# AirScout_SchematicsV2_1.net
KiCad netlist of a schematic drawn in Altium Designer
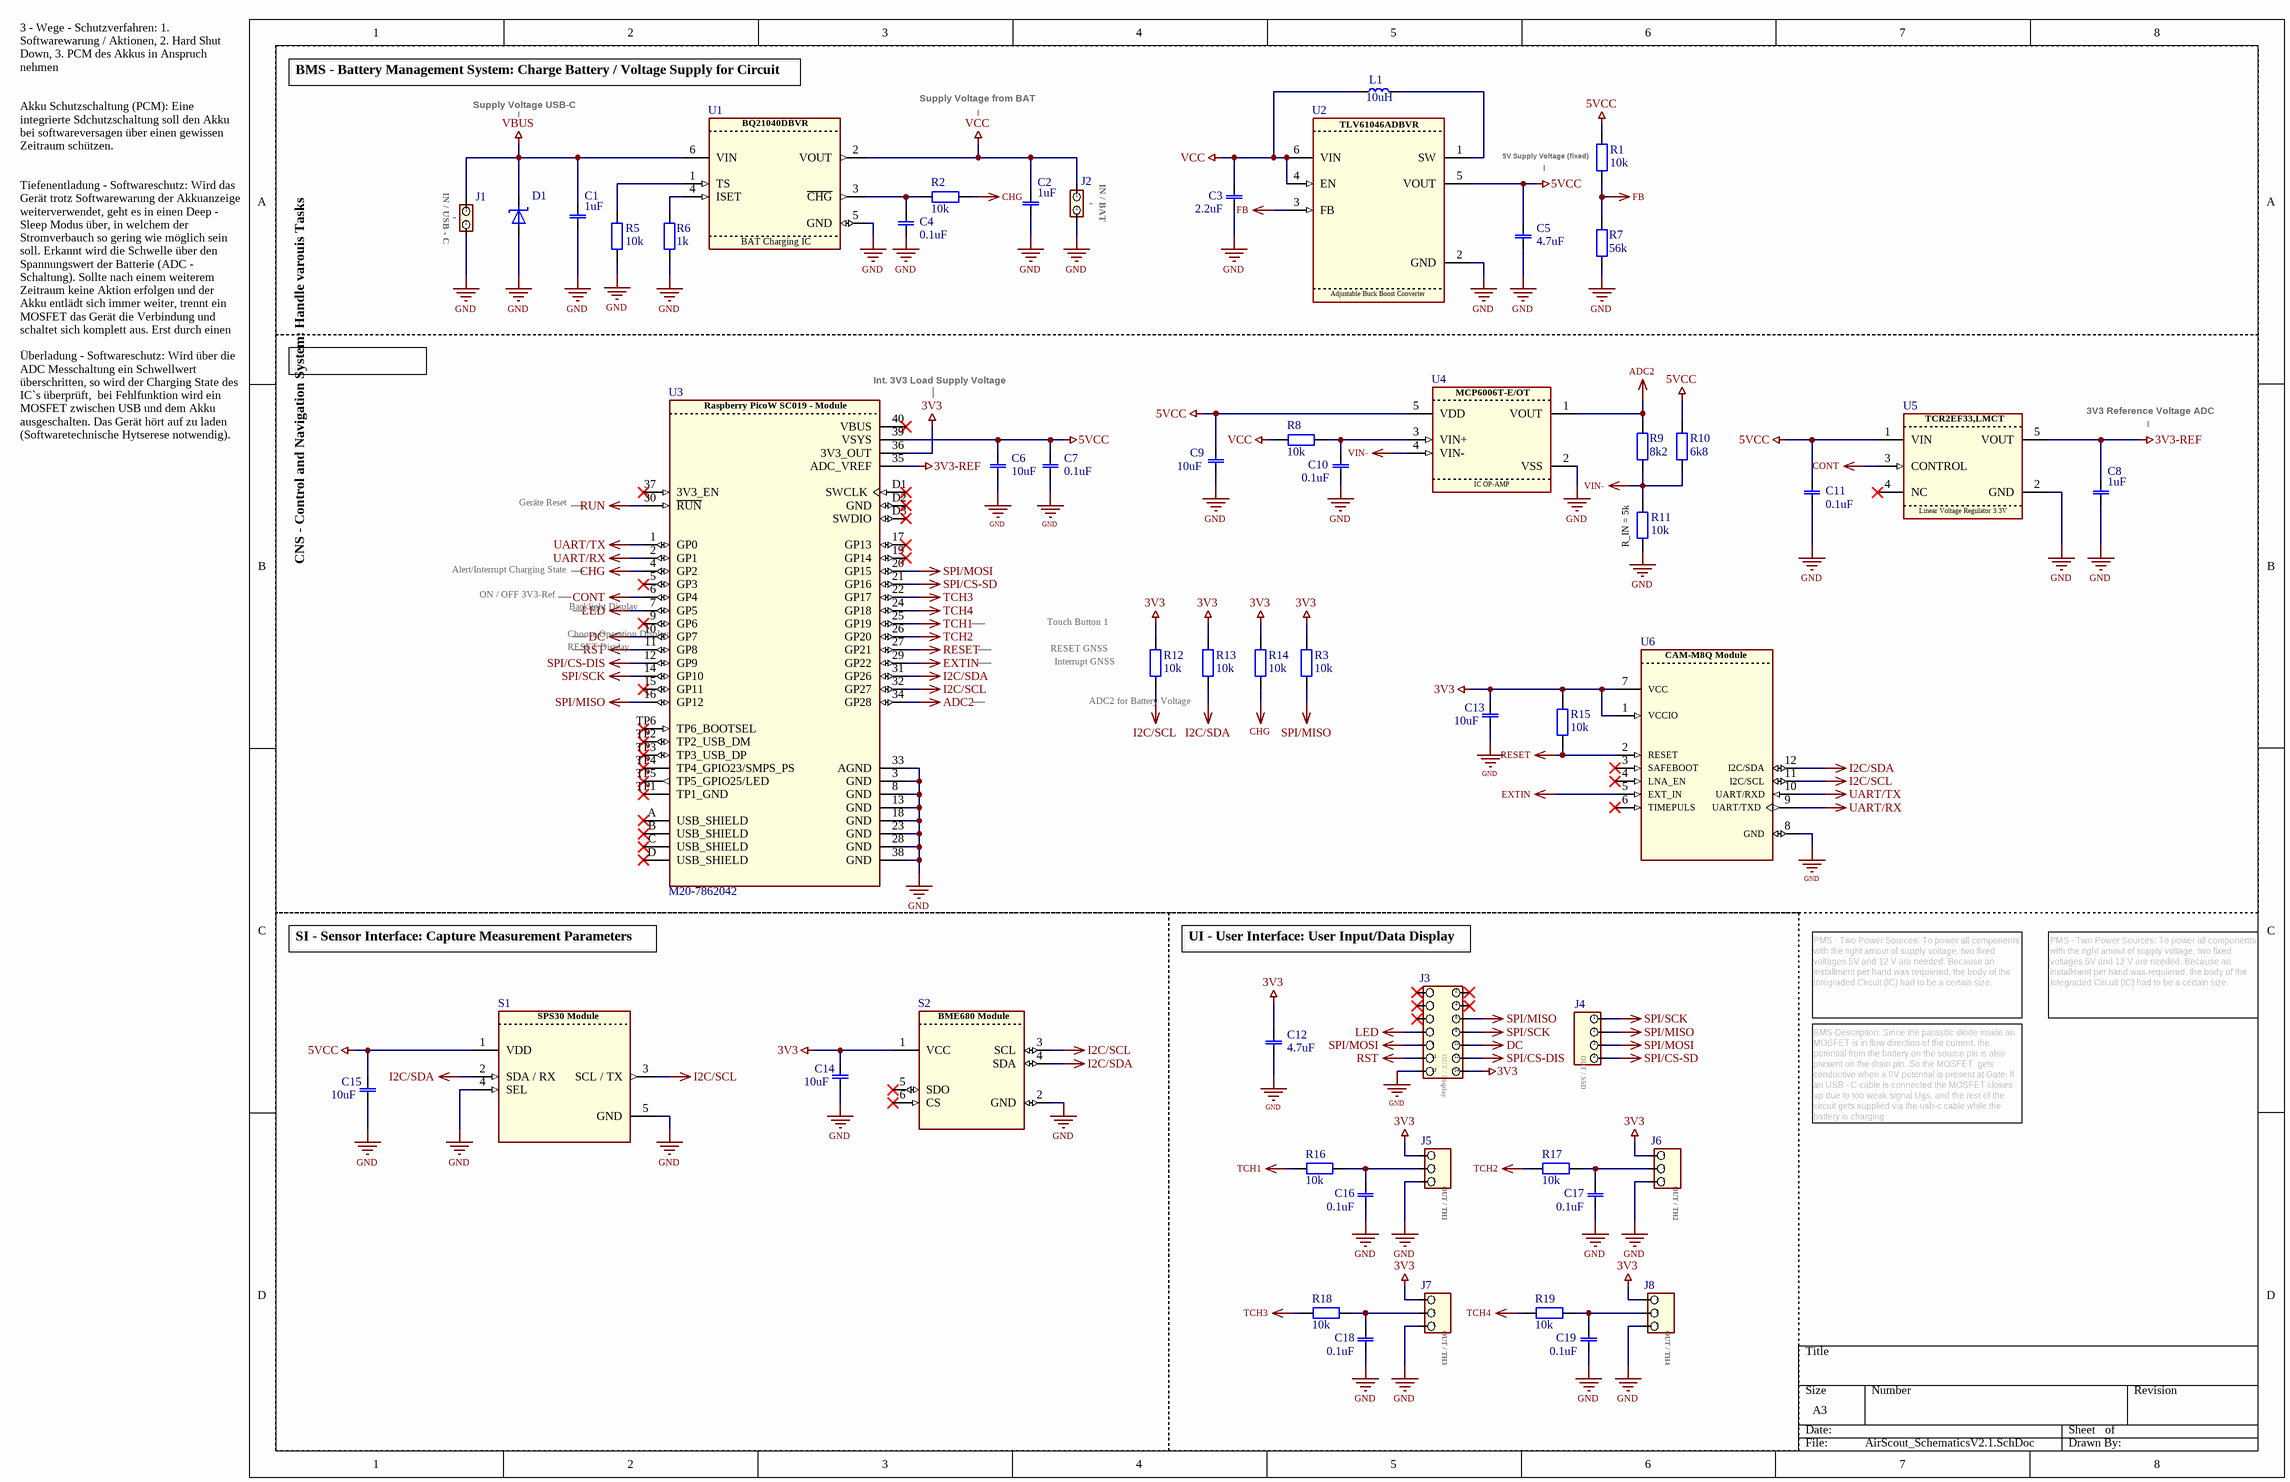
[diagram p0: AirScout_SchematicsV2.1.SchDoc]

(export (version "E")
  (design (tool "Eeschema 10.0.6"))
  (components
    (comp (ref "C1")
      (value "1uF")
      (footprint "CAPC340180_140N_KEM")
      (description "CAP CER 1UF 25V X7R 1206")
      (fields (field (name "Comment") "C1206C105K3RACTU"))
      (libsource (lib "AirScoutSchLibV2.0") (part "CAP"))
    )
    (comp (ref "C2")
      (value "1uF")
      (footprint "CAPC340180_140N_KEM")
      (description "CAP CER 1UF 25V X7R 1206")
      (fields (field (name "Comment") "C1206C105K3RACTU"))
      (libsource (lib "AirScoutSchLibV2.0") (part "CAP"))
    )
    (comp (ref "C3")
      (value "2.2uF")
      (footprint "CAPC340180_140N_KEM")
      (description "CAP CER 2.2UF 50V X7R 1206")
      (fields (field (name "Comment") "CL31B225KBHNNNE"))
      (libsource (lib "AirScoutSchLibV2.0") (part "CAP"))
    )
    (comp (ref "C4")
      (value "0.1uF")
      (footprint "CAPC340180_140N_KEM")
      (description "CAP CER 0.1UF 50V X7R 1206")
      (fields (field (name "Comment") "C1206C104K5RACTU"))
      (libsource (lib "AirScoutSchLibV2.0") (part "CAP"))
    )
    (comp (ref "C5")
      (value "4.7uF")
      (footprint "CAPC340180_140N_KEM")
      (description "CAP CER 4.7UF 50V X7R 1206")
      (fields (field (name "Comment") "CL31B475KBHNFNE"))
      (libsource (lib "AirScoutSchLibV2.0") (part "CAP"))
    )
    (comp (ref "C6")
      (value "10uF")
      (footprint "CAPC340180_140N_KEM")
      (description "CAP CER 10UF 25V X7R 1206")
      (fields (field (name "Comment") "CL31B106KAHNNNE"))
      (libsource (lib "AirScoutSchLibV2.0") (part "CAP"))
    )
    (comp (ref "C7")
      (value "0.1uF")
      (footprint "CAPC340180_140N_KEM")
      (description "CAP CER 0.1UF 50V X7R 1206")
      (fields (field (name "Comment") "C1206C104K5RACTU"))
      (libsource (lib "AirScoutSchLibV2.0") (part "CAP"))
    )
    (comp (ref "C8")
      (value "1uF")
      (footprint "CAPC340180_140N_KEM")
      (description "CAP CER 1UF 25V X7R 1206")
      (fields (field (name "Comment") "C1206C105K3RACTU"))
      (libsource (lib "AirScoutSchLibV2.0") (part "CAP"))
    )
    (comp (ref "C9")
      (value "10uF")
      (footprint "CAPC340180_140N_KEM")
      (description "CAP CER 10UF 25V X7R 1206")
      (fields (field (name "Comment") "CL31B106KAHNNNE"))
      (libsource (lib "AirScoutSchLibV2.0") (part "CAP"))
    )
    (comp (ref "C10")
      (value "0.1uF")
      (footprint "CAPC340180_140N_KEM")
      (description "CAP CER 0.1UF 50V X7R 1206")
      (fields (field (name "Comment") "C1206C104K5RACTU"))
      (libsource (lib "AirScoutSchLibV2.0") (part "CAP"))
    )
    (comp (ref "C11")
      (value "0.1uF")
      (footprint "CAPC340180_140N_KEM")
      (description "CAP CER 0.1UF 50V X7R 1206")
      (fields (field (name "Comment") "C1206C104K5RACTU"))
      (libsource (lib "AirScoutSchLibV2.0") (part "CAP"))
    )
    (comp (ref "C12")
      (value "4.7uF")
      (footprint "CAPC340180_140N_KEM")
      (description "CAP CER 4.7UF 50V X7R 1206")
      (fields (field (name "Comment") "CL31B475KBHNFNE"))
      (libsource (lib "AirScoutSchLibV2.0") (part "CAP"))
    )
    (comp (ref "C13")
      (value "10uF")
      (footprint "CAPC340180_140N_KEM")
      (description "CAP CER 10UF 25V X7R 1206")
      (fields (field (name "Comment") "CL31B106KAHNNNE"))
      (libsource (lib "AirScoutSchLibV2.0") (part "CAP"))
    )
    (comp (ref "C14")
      (value "10uF")
      (footprint "CAPC340180_140N_KEM")
      (description "CAP CER 10UF 25V X7R 1206")
      (fields (field (name "Comment") "CL31B106KAHNNNE"))
      (libsource (lib "AirScoutSchLibV2.0") (part "CAP"))
    )
    (comp (ref "C15")
      (value "10uF")
      (footprint "CAPC340180_140N_KEM")
      (description "CAP CER 10UF 25V X7R 1206")
      (fields (field (name "Comment") "CL31B106KAHNNNE"))
      (libsource (lib "AirScoutSchLibV2.0") (part "CAP"))
    )
    (comp (ref "C16")
      (value "0.1uF")
      (footprint "CAPC340180_140N_KEM")
      (description "CAP CER 0.1UF 50V X7R 1206")
      (fields (field (name "Comment") "C1206C104K5RACTU"))
      (libsource (lib "AirScoutSchLibV2.0") (part "CAP"))
    )
    (comp (ref "C17")
      (value "0.1uF")
      (footprint "CAPC340180_140N_KEM")
      (description "CAP CER 0.1UF 50V X7R 1206")
      (fields (field (name "Comment") "C1206C104K5RACTU"))
      (libsource (lib "AirScoutSchLibV2.0") (part "CAP"))
    )
    (comp (ref "C18")
      (value "0.1uF")
      (footprint "CAPC340180_140N_KEM")
      (description "CAP CER 0.1UF 50V X7R 1206")
      (fields (field (name "Comment") "C1206C104K5RACTU"))
      (libsource (lib "AirScoutSchLibV2.0") (part "CAP"))
    )
    (comp (ref "C19")
      (value "0.1uF")
      (footprint "CAPC340180_140N_KEM")
      (description "CAP CER 0.1UF 50V X7R 1206")
      (fields (field (name "Comment") "C1206C104K5RACTU"))
      (libsource (lib "AirScoutSchLibV2.0") (part "CAP"))
    )
    (comp (ref "D1")
      (value "SMBJ14CA-13-F")
      (footprint "SMB_DIO")
      (description "TVS DIODE 14VWM 23.2VC SMB")
      (libsource (lib "AirScoutSchLibV2.1") (part "Diode-Schottky"))
    )
    (comp (ref "J1")
      (value "S2B-ZR-SM4A-TF")
      (footprint "JST_S2B-ZR-SM4A-TF")
      (description "CONN HEADER SMD R/A 2POS 1.5MM")
      (libsource (lib "AirScoutSchLibV2.2") (part "CON2x1_vertical"))
    )
    (comp (ref "J2")
      (value "S2B-ZR-SM4A-TF")
      (footprint "JST_S2B-ZR-SM4A-TF")
      (description "CONN HEADER SMD R/A 2POS 1.5MM")
      (libsource (lib "AirScoutSchLibV2.2") (part "CON2x1_vertical"))
    )
    (comp (ref "J3")
      (value "IDMS-14-D-02.00-R")
      (footprint "CONN_14POL_SAMTEC")
      (description "Alternitives: IDMS-14-D-03.00, IDMS-14-D-02.00, IDMS-14-D-03.00-R")
      (libsource (lib "AirScoutSchLibV2.0") (part "CON7x2"))
    )
    (comp (ref "J4")
      (value "IDMS-4-D-02.00-R")
      (footprint "SAMTEC_IDMS-04-S-02.00")
      (description "Alternitives:  IDMS-4-D-03.00, IDMS-4-D-02.00, IDMS-4-D-03.00-R")
      (libsource (lib "AirScoutSchLibV2.0") (part "CON 4x1"))
    )
    (comp (ref "J5")
      (value "IDMS-3-D-02.00-R")
      (footprint "CONN_3POL_SAMTEC")
      (description "Alternitives:  IDMS-3-D-03.00, IDMS-3-D-02.00, IDMS-3-D-03.00-R")
      (libsource (lib "AirScoutSchLibV2.0") (part "CON 3x1"))
    )
    (comp (ref "J6")
      (value "IDMS-3-D-02.00-R")
      (footprint "CONN_3POL_SAMTEC")
      (description "Alternitives:  IDMS-3-D-03.00, IDMS-3-D-02.00, IDMS-3-D-03.00-R")
      (libsource (lib "AirScoutSchLibV2.0") (part "CON 3x1"))
    )
    (comp (ref "J7")
      (value "IDMS-3-D-02.00-R")
      (footprint "CONN_3POL_SAMTEC")
      (description "Alternitives:  IDMS-3-D-03.00, IDMS-3-D-02.00, IDMS-3-D-03.00-R")
      (libsource (lib "AirScoutSchLibV2.0") (part "CON 3x1"))
    )
    (comp (ref "J8")
      (value "IDMS-3-D-02.00-R")
      (footprint "CONN_3POL_SAMTEC")
      (description "Alternitives:  IDMS-3-D-03.00, IDMS-3-D-02.00, IDMS-3-D-03.00-R")
      (libsource (lib "AirScoutSchLibV2.0") (part "CON 3x1"))
    )
    (comp (ref "L1")
      (value "10uH")
      (footprint "IND_FDSD0420-H-100M=P3")
      (description "FIXED IND 10UH 2A 216 MOHM SMD; \r\nAIUR-05-100K")
      (fields (field (name "Comment") "PA4332.103NLT"))
      (libsource (lib "AirScoutSchLibV2.0") (part "Inductor"))
    )
    (comp (ref "R1")
      (value "10k")
      (footprint "RESC3116X65N")
      (description "RES 10K OHM 1% 1/4W 1206")
      (fields (field (name "Comment") "RC1206FR-0710KL"))
      (libsource (lib "AirScoutSchLibV2.0") (part "RES"))
    )
    (comp (ref "R2")
      (value "10k")
      (footprint "RESC3116X65N")
      (description "RES 10K OHM 1% 1/4W 1206")
      (fields (field (name "Comment") "RC1206FR-0710KL"))
      (libsource (lib "AirScoutSchLibV2.0") (part "RES"))
    )
    (comp (ref "R3")
      (value "10k")
      (footprint "RESC3116X65N")
      (description "RES 10K OHM 1% 1/4W 1206")
      (fields (field (name "Comment") "RC1206FR-0710KL"))
      (libsource (lib "AirScoutSchLibV2.0") (part "RES"))
    )
    (comp (ref "R5")
      (value "10k")
      (footprint "RESC3116X65N")
      (description "RES 10K OHM 1% 1/4W 1206")
      (fields (field (name "Comment") "RC1206FR-0710KL"))
      (libsource (lib "AirScoutSchLibV2.0") (part "RES"))
    )
    (comp (ref "R6")
      (value "1k")
      (footprint "RESC3116X65N")
      (description "RES 1K OHM 1% 1/2W 1206")
      (fields (field (name "Comment") "RNCP1206FTD1K00"))
      (libsource (lib "AirScoutSchLibV2.0") (part "RES"))
    )
    (comp (ref "R7")
      (value "56k")
      (footprint "RESC3116X65N")
      (description "RES 56K OHM 5% 1/4W 1206")
      (fields (field (name "Comment") "RMCF1206JT56K0"))
      (libsource (lib "AirScoutSchLibV2.0") (part "RES"))
    )
    (comp (ref "R8")
      (value "10k")
      (footprint "RESC3116X65N")
      (description "RES 10K OHM 1% 1/4W 1206")
      (fields (field (name "Comment") "RC1206FR-0710KL"))
      (libsource (lib "AirScoutSchLibV2.0") (part "RES"))
    )
    (comp (ref "R9")
      (value "8k2")
      (footprint "RESC3116X65N")
      (description "RES 200K OHM 5% 1/4W 1206")
      (fields (field (name "Comment") "RC1206JR-07200KL"))
      (libsource (lib "AirScoutSchLibV2.0") (part "RES"))
    )
    (comp (ref "R10")
      (value "6k8")
      (footprint "RESC3116X65N")
      (description "RES 220K OHM 5% 1/4W 1206")
      (fields (field (name "Comment") "RC1206JR-07220KL"))
      (libsource (lib "AirScoutSchLibV2.0") (part "RES"))
    )
    (comp (ref "R11")
      (value "10k")
      (footprint "RESC3116X65N")
      (description "RES 220K OHM 5% 1/4W 1206")
      (fields (field (name "Comment") "RC1206JR-07220KL"))
      (libsource (lib "AirScoutSchLibV2.0") (part "RES"))
    )
    (comp (ref "R12")
      (value "10k")
      (footprint "RESC3116X65N")
      (description "RES 10K OHM 1% 1/4W 1206")
      (fields (field (name "Comment") "RC1206FR-0710KL"))
      (libsource (lib "AirScoutSchLibV2.0") (part "RES"))
    )
    (comp (ref "R13")
      (value "10k")
      (footprint "RESC3116X65N")
      (description "RES 10K OHM 1% 1/4W 1206")
      (fields (field (name "Comment") "RC1206FR-0710KL"))
      (libsource (lib "AirScoutSchLibV2.0") (part "RES"))
    )
    (comp (ref "R14")
      (value "10k")
      (footprint "RESC3116X65N")
      (description "RES 10K OHM 1% 1/4W 1206")
      (fields (field (name "Comment") "RC1206FR-0710KL"))
      (libsource (lib "AirScoutSchLibV2.0") (part "RES"))
    )
    (comp (ref "R15")
      (value "10k")
      (footprint "RESC3116X65N")
      (description "RES 10K OHM 1% 1/4W 1206")
      (fields (field (name "Comment") "RC1206FR-0710KL"))
      (libsource (lib "AirScoutSchLibV2.0") (part "RES"))
    )
    (comp (ref "R16")
      (value "10k")
      (footprint "RESC3116X65N")
      (description "RES 10K OHM 1% 1/4W 1206")
      (fields (field (name "Comment") "RC1206FR-0710KL"))
      (libsource (lib "AirScoutSchLibV2.0") (part "RES"))
    )
    (comp (ref "R17")
      (value "10k")
      (footprint "RESC3116X65N")
      (description "RES 10K OHM 1% 1/4W 1206")
      (fields (field (name "Comment") "RC1206FR-0710KL"))
      (libsource (lib "AirScoutSchLibV2.0") (part "RES"))
    )
    (comp (ref "R18")
      (value "10k")
      (footprint "RESC3116X65N")
      (description "RES 10K OHM 1% 1/4W 1206")
      (fields (field (name "Comment") "RC1206FR-0710KL"))
      (libsource (lib "AirScoutSchLibV2.0") (part "RES"))
    )
    (comp (ref "R19")
      (value "10k")
      (footprint "RESC3116X65N")
      (description "RES 10K OHM 1% 1/4W 1206")
      (fields (field (name "Comment") "RC1206FR-0710KL"))
      (libsource (lib "AirScoutSchLibV2.0") (part "RES"))
    )
    (comp (ref "S1")
      (value "B5B-ZR")
      (footprint "CONN5_B5B-ZR_JST")
      (description "Plug: CONN HEADER VERT 5POS 1.5MM; Air Sensor Dust Sensor Box SPS30 Module: 1649-1106-ND")
      (libsource (lib "AirScoutSchLibV2.0") (part "SPS30 Module"))
    )
    (comp (ref "S2")
      (value "NPPC061KFXC-RC")
      (footprint "PIM357")
      (libsource (lib "AirScoutSchLibV2.0") (part "BME680 Module"))
    )
    (comp (ref "U1")
      (value "BQ21040DBVR")
      (footprint "SOT95P280X145-6N")
      (fields (field (name "MF") "Texas Instruments"))
      (libsource (lib "AirScoutSchLibV2.0") (part "BQ21040DBVR"))
    )
    (comp (ref "U2")
      (value "TLV61046ADBVR")
      (footprint "DBV0006A_M")
      (description "28-V Output Voltage Boost Converter with Power Diode and Isolation Switch 6-SOT-23 -40 to 125")
      (fields (field (name "COPYRIGHT") "Copyright (C) 2025 Ultra Librarian. All rights reserved."))
      (libsource (lib "AirScoutSchLibV2.0") (part "TLV61046ADBVR"))
    )
    (comp (ref "U3")
      (value "M20-7862042")
      (footprint "PicoW SC019")
      (description "(2x) CONN RECPT 2.54MM SMT 20POS; PicoW: SC0918; RASPBERRY PI PICO W RP2040")
      (libsource (lib "AirScoutSchLibV2.1") (part "Raspberry PicoW SC019 Module"))
    )
    (comp (ref "U4")
      (value "MCP6006T-E/OT")
      (footprint "SOT23-5-AP2202K_DIO-M")
      (description "IC OPAMP GP 1 CIRCUIT SOT23-5")
      (libsource (lib "AirScoutSchLibV2.0") (part "MCP6006T-E/OT"))
    )
    (comp (ref "U5")
      (value "TCR2EF33,LM(CT")
      (footprint "SOT-25   SMV_TOS")
      (description "IC REG LINEAR 3.3V 200MA SMV")
      (fields (field (name "COPYRIGHT") "Copyright (C) 2025 Ultra Librarian. All rights reserved."))
      (libsource (lib "AirScoutSchLibV2.0") (part "TCR2EF33,LMCT"))
    )
    (comp (ref "U6")
      (value "NPPC061KFXC-RC")
      (footprint "CAM8MQ-Mod")
      (description "(2x) CONN HDR 6POS 0.1 GOLD SMD; GPS - Module:  201880; CAM-M8Q-BREAKOUT MULTI GNSS MODU")
      (libsource (lib "AirScoutSchLibV2.0") (part "CAM-M8Q Module"))
    )
  )
  (nets
    (net (code "1") (name "3V3") (class "Default")
      (node (ref "C12") (pin "2") (pinfunction "2_2") (pintype "passive"))
      (node (ref "C13") (pin "2") (pinfunction "2_2") (pintype "passive"))
      (node (ref "C14") (pin "2") (pinfunction "2_2") (pintype "passive"))
      (node (ref "J3") (pin "14") (pinfunction "14_14") (pintype "passive"))
      (node (ref "J5") (pin "1") (pinfunction "1_1") (pintype "passive"))
      (node (ref "J6") (pin "1") (pinfunction "1_1") (pintype "passive"))
      (node (ref "J7") (pin "1") (pinfunction "1_1") (pintype "passive"))
      (node (ref "J8") (pin "1") (pinfunction "1_1") (pintype "passive"))
      (node (ref "R12") (pin "2") (pinfunction "2_2") (pintype "passive"))
      (node (ref "R13") (pin "2") (pinfunction "2_2") (pintype "passive"))
      (node (ref "R14") (pin "2") (pinfunction "2_2") (pintype "passive"))
      (node (ref "R15") (pin "2") (pinfunction "2_2") (pintype "passive"))
      (node (ref "R3") (pin "2") (pinfunction "2_2") (pintype "passive"))
      (node (ref "S2") (pin "1") (pinfunction "VCC_1") (pintype "power_in"))
      (node (ref "U3") (pin "36") (pinfunction "3V3_OUT_36") (pintype "power_in"))
      (node (ref "U6") (pin "1") (pinfunction "VCCIO_1") (pintype "input"))
      (node (ref "U6") (pin "7") (pinfunction "VCC_7") (pintype "power_in"))
    )
    (net (code "2") (name "3V3-REF") (class "Default")
      (node (ref "C8") (pin "2") (pinfunction "2_2") (pintype "passive"))
      (node (ref "U3") (pin "35") (pinfunction "ADC_VREF_35") (pintype "power_in"))
      (node (ref "U5") (pin "5") (pinfunction "VOUT_5") (pintype "power_in"))
    )
    (net (code "3") (name "5VCC") (class "Default")
      (node (ref "C11") (pin "2") (pinfunction "2_2") (pintype "passive"))
      (node (ref "C15") (pin "2") (pinfunction "2_2") (pintype "passive"))
      (node (ref "C5") (pin "2") (pinfunction "2_2") (pintype "passive"))
      (node (ref "C6") (pin "2") (pinfunction "2_2") (pintype "passive"))
      (node (ref "C7") (pin "2") (pinfunction "2_2") (pintype "passive"))
      (node (ref "C9") (pin "2") (pinfunction "2_2") (pintype "passive"))
      (node (ref "R1") (pin "2") (pinfunction "2_2") (pintype "passive"))
      (node (ref "R10") (pin "2") (pinfunction "2_2") (pintype "passive"))
      (node (ref "S1") (pin "1") (pinfunction "VDD_1") (pintype "passive"))
      (node (ref "U2") (pin "5") (pinfunction "VOUT_5") (pintype "power_in"))
      (node (ref "U3") (pin "39") (pinfunction "VSYS_39") (pintype "power_in"))
      (node (ref "U4") (pin "5") (pinfunction "VDD_5") (pintype "power_in"))
      (node (ref "U5") (pin "1") (pinfunction "VIN_1") (pintype "power_in"))
    )
    (net (code "4") (name "ADC2") (class "Default")
      (node (ref "R9") (pin "2") (pinfunction "2_2") (pintype "passive"))
      (node (ref "U3") (pin "34") (pinfunction "GP28_34") (pintype "bidirectional"))
      (node (ref "U4") (pin "1") (pinfunction "VOUT_1") (pintype "power_in"))
    )
    (net (code "5") (name "CHG") (class "Default")
      (node (ref "R14") (pin "1") (pinfunction "1_1") (pintype "passive"))
      (node (ref "R2") (pin "1") (pinfunction "1_1") (pintype "passive"))
      (node (ref "U3") (pin "4") (pinfunction "GP2_4") (pintype "bidirectional"))
    )
    (net (code "6") (name "CONT") (class "Default")
      (node (ref "U3") (pin "6") (pinfunction "GP4_6") (pintype "bidirectional"))
      (node (ref "U5") (pin "3") (pinfunction "CONTROL_3") (pintype "input"))
    )
    (net (code "7") (name "DC") (class "Default")
      (node (ref "J3") (pin "10") (pinfunction "10_10") (pintype "passive"))
      (node (ref "U3") (pin "10") (pinfunction "GP7_10") (pintype "bidirectional"))
    )
    (net (code "8") (name "EXTIN") (class "Default")
      (node (ref "U3") (pin "29") (pinfunction "GP22_29") (pintype "bidirectional"))
      (node (ref "U6") (pin "5") (pinfunction "EXT_IN_5") (pintype "input"))
    )
    (net (code "9") (name "FB") (class "Default")
      (node (ref "R1") (pin "1") (pinfunction "1_1") (pintype "passive"))
      (node (ref "R7") (pin "2") (pinfunction "2_2") (pintype "passive"))
      (node (ref "U2") (pin "3") (pinfunction "FB_3") (pintype "input"))
    )
    (net (code "10") (name "GND") (class "Default")
      (node (ref "C1") (pin "1") (pinfunction "1_1") (pintype "passive"))
      (node (ref "C10") (pin "1") (pinfunction "1_1") (pintype "passive"))
      (node (ref "C11") (pin "1") (pinfunction "1_1") (pintype "passive"))
      (node (ref "C12") (pin "1") (pinfunction "1_1") (pintype "passive"))
      (node (ref "C13") (pin "1") (pinfunction "1_1") (pintype "passive"))
      (node (ref "C14") (pin "1") (pinfunction "1_1") (pintype "passive"))
      (node (ref "C15") (pin "1") (pinfunction "1_1") (pintype "passive"))
      (node (ref "C16") (pin "1") (pinfunction "1_1") (pintype "passive"))
      (node (ref "C17") (pin "1") (pinfunction "1_1") (pintype "passive"))
      (node (ref "C18") (pin "1") (pinfunction "1_1") (pintype "passive"))
      (node (ref "C19") (pin "1") (pinfunction "1_1") (pintype "passive"))
      (node (ref "C2") (pin "1") (pinfunction "1_1") (pintype "passive"))
      (node (ref "C3") (pin "1") (pinfunction "1_1") (pintype "passive"))
      (node (ref "C4") (pin "1") (pinfunction "1_1") (pintype "passive"))
      (node (ref "C5") (pin "1") (pinfunction "1_1") (pintype "passive"))
      (node (ref "C6") (pin "1") (pinfunction "1_1") (pintype "passive"))
      (node (ref "C7") (pin "1") (pinfunction "1_1") (pintype "passive"))
      (node (ref "C8") (pin "1") (pinfunction "1_1") (pintype "passive"))
      (node (ref "C9") (pin "1") (pinfunction "1_1") (pintype "passive"))
      (node (ref "D1") (pin "A") (pinfunction "A_A") (pintype "passive"))
      (node (ref "J1") (pin "2") (pinfunction "-_2") (pintype "passive"))
      (node (ref "J2") (pin "2") (pinfunction "-_2") (pintype "passive"))
      (node (ref "J3") (pin "13") (pinfunction "13_13") (pintype "passive"))
      (node (ref "J5") (pin "3") (pinfunction "3_3") (pintype "passive"))
      (node (ref "J6") (pin "3") (pinfunction "3_3") (pintype "passive"))
      (node (ref "J7") (pin "3") (pinfunction "3_3") (pintype "passive"))
      (node (ref "J8") (pin "3") (pinfunction "3_3") (pintype "passive"))
      (node (ref "R11") (pin "1") (pinfunction "1_1") (pintype "passive"))
      (node (ref "R5") (pin "1") (pinfunction "1_1") (pintype "passive"))
      (node (ref "R6") (pin "1") (pinfunction "1_1") (pintype "passive"))
      (node (ref "R7") (pin "1") (pinfunction "1_1") (pintype "passive"))
      (node (ref "S1") (pin "4") (pinfunction "SEL_4") (pintype "input"))
      (node (ref "S1") (pin "5") (pinfunction "GND_5") (pintype "passive"))
      (node (ref "S2") (pin "2") (pinfunction "GND_2") (pintype "bidirectional"))
      (node (ref "U1") (pin "5") (pinfunction "GND_5") (pintype "bidirectional"))
      (node (ref "U2") (pin "2") (pinfunction "GND_2") (pintype "power_in"))
      (node (ref "U3") (pin "13") (pinfunction "GND_13") (pintype "power_in"))
      (node (ref "U3") (pin "18") (pinfunction "GND_18") (pintype "power_in"))
      (node (ref "U3") (pin "23") (pinfunction "GND_23") (pintype "power_in"))
      (node (ref "U3") (pin "28") (pinfunction "GND_28") (pintype "power_in"))
      (node (ref "U3") (pin "3") (pinfunction "GND_3") (pintype "power_in"))
      (node (ref "U3") (pin "33") (pinfunction "AGND_33") (pintype "power_in"))
      (node (ref "U3") (pin "38") (pinfunction "GND_38") (pintype "power_in"))
      (node (ref "U3") (pin "8") (pinfunction "GND_8") (pintype "power_in"))
      (node (ref "U4") (pin "2") (pinfunction "VSS_2") (pintype "power_in"))
      (node (ref "U5") (pin "2") (pinfunction "GND_2") (pintype "power_in"))
      (node (ref "U6") (pin "8") (pinfunction "GND_8") (pintype "bidirectional"))
    )
    (net (code "11") (name "I2C{slash}SCL") (class "Default")
      (node (ref "R12") (pin "1") (pinfunction "1_1") (pintype "passive"))
      (node (ref "S1") (pin "3") (pinfunction "SCL_/_TX_3") (pintype "output"))
      (node (ref "S2") (pin "3") (pinfunction "SCL_3") (pintype "bidirectional"))
      (node (ref "U3") (pin "32") (pinfunction "GP27_32") (pintype "bidirectional"))
      (node (ref "U6") (pin "11") (pinfunction "I2C/SCL_11") (pintype "bidirectional"))
    )
    (net (code "12") (name "I2C{slash}SDA") (class "Default")
      (node (ref "R13") (pin "1") (pinfunction "1_1") (pintype "passive"))
      (node (ref "S1") (pin "2") (pinfunction "SDA_/_RX_2") (pintype "input"))
      (node (ref "S2") (pin "4") (pinfunction "SDA_4") (pintype "bidirectional"))
      (node (ref "U3") (pin "31") (pinfunction "GP26_31") (pintype "bidirectional"))
      (node (ref "U6") (pin "12") (pinfunction "I2C/SDA_12") (pintype "bidirectional"))
    )
    (net (code "13") (name "LED") (class "Default")
      (node (ref "J3") (pin "7") (pinfunction "7_7") (pintype "passive"))
      (node (ref "U3") (pin "7") (pinfunction "GP5_7") (pintype "bidirectional"))
    )
    (net (code "14") (name "Net-(C16-Pad2)") (class "Default")
      (node (ref "C16") (pin "2") (pinfunction "2_2") (pintype "passive"))
      (node (ref "J5") (pin "2") (pinfunction "2_2") (pintype "passive"))
      (node (ref "R16") (pin "1") (pinfunction "1_1") (pintype "passive"))
    )
    (net (code "15") (name "Net-(C17-Pad2)") (class "Default")
      (node (ref "C17") (pin "2") (pinfunction "2_2") (pintype "passive"))
      (node (ref "J6") (pin "2") (pinfunction "2_2") (pintype "passive"))
      (node (ref "R17") (pin "1") (pinfunction "1_1") (pintype "passive"))
    )
    (net (code "16") (name "Net-(C18-Pad2)") (class "Default")
      (node (ref "C18") (pin "2") (pinfunction "2_2") (pintype "passive"))
      (node (ref "J7") (pin "2") (pinfunction "2_2") (pintype "passive"))
      (node (ref "R18") (pin "1") (pinfunction "1_1") (pintype "passive"))
    )
    (net (code "17") (name "Net-(C19-Pad2)") (class "Default")
      (node (ref "C19") (pin "2") (pinfunction "2_2") (pintype "passive"))
      (node (ref "J8") (pin "2") (pinfunction "2_2") (pintype "passive"))
      (node (ref "R19") (pin "1") (pinfunction "1_1") (pintype "passive"))
    )
    (net (code "18") (name "Net-(U1-ISET)") (class "Default")
      (node (ref "R6") (pin "2") (pinfunction "2_2") (pintype "passive"))
      (node (ref "U1") (pin "4") (pinfunction "ISET_4") (pintype "input"))
    )
    (net (code "19") (name "Net-(U1-TS)") (class "Default")
      (node (ref "R5") (pin "2") (pinfunction "2_2") (pintype "passive"))
      (node (ref "U1") (pin "1") (pinfunction "TS_1") (pintype "input"))
    )
    (net (code "20") (name "Net-(U1-~{CHG})") (class "Default")
      (node (ref "C4") (pin "2") (pinfunction "2_2") (pintype "passive"))
      (node (ref "R2") (pin "2") (pinfunction "2_2") (pintype "passive"))
      (node (ref "U1") (pin "3") (pinfunction "~{CHG}_3") (pintype "output"))
    )
    (net (code "21") (name "Net-(U2-SW)") (class "Default")
      (node (ref "L1") (pin "2") (pinfunction "2_2") (pintype "passive"))
      (node (ref "U2") (pin "1") (pinfunction "SW_1") (pintype "power_in"))
    )
    (net (code "22") (name "Net-(U4-VIN+)") (class "Default")
      (node (ref "C10") (pin "2") (pinfunction "2_2") (pintype "passive"))
      (node (ref "R8") (pin "1") (pinfunction "1_1") (pintype "passive"))
      (node (ref "U4") (pin "3") (pinfunction "VIN+_3") (pintype "input"))
    )
    (net (code "23") (name "RESET") (class "Default")
      (node (ref "R15") (pin "1") (pinfunction "1_1") (pintype "passive"))
      (node (ref "U3") (pin "27") (pinfunction "GP21_27") (pintype "bidirectional"))
      (node (ref "U6") (pin "2") (pinfunction "RESET_2") (pintype "input"))
    )
    (net (code "24") (name "RST") (class "Default")
      (node (ref "J3") (pin "11") (pinfunction "11_11") (pintype "passive"))
      (node (ref "U3") (pin "11") (pinfunction "GP8_11") (pintype "bidirectional"))
    )
    (net (code "25") (name "RUN") (class "Default")
      (node (ref "U3") (pin "30") (pinfunction "~{RUN}_30") (pintype "input"))
    )
    (net (code "26") (name "SPI{slash}CS-DIS") (class "Default")
      (node (ref "J3") (pin "12") (pinfunction "12_12") (pintype "passive"))
      (node (ref "U3") (pin "12") (pinfunction "GP9_12") (pintype "bidirectional"))
    )
    (net (code "27") (name "SPI{slash}CS-SD") (class "Default")
      (node (ref "J4") (pin "4") (pinfunction "4_4") (pintype "passive"))
      (node (ref "U3") (pin "21") (pinfunction "GP16_21") (pintype "bidirectional"))
    )
    (net (code "28") (name "SPI{slash}MISO") (class "Default")
      (node (ref "J3") (pin "6") (pinfunction "6_6") (pintype "passive"))
      (node (ref "J4") (pin "2") (pinfunction "2_2") (pintype "passive"))
      (node (ref "R3") (pin "1") (pinfunction "1_1") (pintype "passive"))
      (node (ref "U3") (pin "16") (pinfunction "GP12_16") (pintype "bidirectional"))
    )
    (net (code "29") (name "SPI{slash}MOSI") (class "Default")
      (node (ref "J3") (pin "9") (pinfunction "9_9") (pintype "passive"))
      (node (ref "J4") (pin "3") (pinfunction "3_3") (pintype "passive"))
      (node (ref "U3") (pin "20") (pinfunction "GP15_20") (pintype "bidirectional"))
    )
    (net (code "30") (name "SPI{slash}SCK") (class "Default")
      (node (ref "J3") (pin "8") (pinfunction "8_8") (pintype "passive"))
      (node (ref "J4") (pin "1") (pinfunction "1_1") (pintype "passive"))
      (node (ref "U3") (pin "14") (pinfunction "GP10_14") (pintype "bidirectional"))
    )
    (net (code "31") (name "TCH1") (class "Default")
      (node (ref "R16") (pin "2") (pinfunction "2_2") (pintype "passive"))
      (node (ref "U3") (pin "25") (pinfunction "GP19_25") (pintype "bidirectional"))
    )
    (net (code "32") (name "TCH2") (class "Default")
      (node (ref "R17") (pin "2") (pinfunction "2_2") (pintype "passive"))
      (node (ref "U3") (pin "26") (pinfunction "GP20_26") (pintype "bidirectional"))
    )
    (net (code "33") (name "TCH3") (class "Default")
      (node (ref "R18") (pin "2") (pinfunction "2_2") (pintype "passive"))
      (node (ref "U3") (pin "22") (pinfunction "GP17_22") (pintype "bidirectional"))
    )
    (net (code "34") (name "TCH4") (class "Default")
      (node (ref "R19") (pin "2") (pinfunction "2_2") (pintype "passive"))
      (node (ref "U3") (pin "24") (pinfunction "GP18_24") (pintype "bidirectional"))
    )
    (net (code "35") (name "UART{slash}RX") (class "Default")
      (node (ref "U3") (pin "2") (pinfunction "GP1_2") (pintype "bidirectional"))
      (node (ref "U6") (pin "9") (pinfunction "UART/TXD_9") (pintype "output"))
    )
    (net (code "36") (name "UART{slash}TX") (class "Default")
      (node (ref "U3") (pin "1") (pinfunction "GP0_1") (pintype "bidirectional"))
      (node (ref "U6") (pin "10") (pinfunction "UART/RXD_10") (pintype "input"))
    )
    (net (code "37") (name "VBUS") (class "Default")
      (node (ref "C1") (pin "2") (pinfunction "2_2") (pintype "passive"))
      (node (ref "D1") (pin "K") (pinfunction "K_K") (pintype "passive"))
      (node (ref "J1") (pin "1") (pinfunction "+_1") (pintype "passive"))
      (node (ref "U1") (pin "6") (pinfunction "VIN_6") (pintype "power_in"))
    )
    (net (code "39") (name "VCC") (class "Default")
      (node (ref "C2") (pin "2") (pinfunction "2_2") (pintype "passive"))
      (node (ref "C3") (pin "2") (pinfunction "2_2") (pintype "passive"))
      (node (ref "J2") (pin "1") (pinfunction "+_1") (pintype "passive"))
      (node (ref "L1") (pin "1") (pinfunction "1_1") (pintype "passive"))
      (node (ref "R8") (pin "2") (pinfunction "2_2") (pintype "passive"))
      (node (ref "U1") (pin "2") (pinfunction "VOUT_2") (pintype "output"))
      (node (ref "U2") (pin "4") (pinfunction "EN_4") (pintype "input"))
      (node (ref "U2") (pin "6") (pinfunction "VIN_6") (pintype "power_in"))
    )
    (net (code "40") (name "VIN-") (class "Default")
      (node (ref "R10") (pin "1") (pinfunction "1_1") (pintype "passive"))
      (node (ref "R11") (pin "2") (pinfunction "2_2") (pintype "passive"))
      (node (ref "R9") (pin "1") (pinfunction "1_1") (pintype "passive"))
      (node (ref "U4") (pin "4") (pinfunction "VIN-_4") (pintype "input"))
    )
    (net (code "41") (name "unconnected-(J3-Pad1)") (class "Default")
      (node (ref "J3") (pin "1") (pinfunction "1_1") (pintype "passive+no_connect"))
    )
    (net (code "42") (name "unconnected-(J3-Pad2)") (class "Default")
      (node (ref "J3") (pin "2") (pinfunction "2_2") (pintype "passive+no_connect"))
    )
    (net (code "43") (name "unconnected-(J3-Pad3)") (class "Default")
      (node (ref "J3") (pin "3") (pinfunction "3_3") (pintype "passive+no_connect"))
    )
    (net (code "44") (name "unconnected-(J3-Pad4)") (class "Default")
      (node (ref "J3") (pin "4") (pinfunction "4_4") (pintype "passive+no_connect"))
    )
    (net (code "45") (name "unconnected-(J3-Pad5)") (class "Default")
      (node (ref "J3") (pin "5") (pinfunction "5_5") (pintype "passive+no_connect"))
    )
    (net (code "46") (name "unconnected-(S2-CS-Pad6)") (class "Default")
      (node (ref "S2") (pin "6") (pinfunction "CS_6") (pintype "input+no_connect"))
    )
    (net (code "47") (name "unconnected-(S2-SDO-Pad5)") (class "Default")
      (node (ref "S2") (pin "5") (pinfunction "SDO_5") (pintype "bidirectional+no_connect"))
    )
    (net (code "48") (name "unconnected-(U3-3V3_EN-Pad37)") (class "Default")
      (node (ref "U3") (pin "37") (pinfunction "3V3_EN_37") (pintype "input+no_connect"))
    )
    (net (code "49") (name "unconnected-(U3-GND-PadD2)") (class "Default")
      (node (ref "U3") (pin "D2") (pinfunction "GND_D2") (pintype "bidirectional+no_connect"))
    )
    (net (code "50") (name "unconnected-(U3-GP3-Pad5)") (class "Default")
      (node (ref "U3") (pin "5") (pinfunction "GP3_5") (pintype "bidirectional+no_connect"))
    )
    (net (code "51") (name "unconnected-(U3-GP6-Pad9)") (class "Default")
      (node (ref "U3") (pin "9") (pinfunction "GP6_9") (pintype "bidirectional+no_connect"))
    )
    (net (code "52") (name "unconnected-(U3-GP11-Pad15)") (class "Default")
      (node (ref "U3") (pin "15") (pinfunction "GP11_15") (pintype "bidirectional+no_connect"))
    )
    (net (code "53") (name "unconnected-(U3-GP13-Pad17)") (class "Default")
      (node (ref "U3") (pin "17") (pinfunction "GP13_17") (pintype "bidirectional+no_connect"))
    )
    (net (code "54") (name "unconnected-(U3-GP14-Pad19)") (class "Default")
      (node (ref "U3") (pin "19") (pinfunction "GP14_19") (pintype "bidirectional+no_connect"))
    )
    (net (code "55") (name "unconnected-(U3-SWCLK-PadD1)") (class "Default")
      (node (ref "U3") (pin "D1") (pinfunction "SWCLK_D1") (pintype "input+no_connect"))
    )
    (net (code "56") (name "unconnected-(U3-SWDIO-PadD3)") (class "Default")
      (node (ref "U3") (pin "D3") (pinfunction "SWDIO_D3") (pintype "bidirectional+no_connect"))
    )
    (net (code "57") (name "unconnected-(U3-TP1_GND-PadTP1)") (class "Default")
      (node (ref "U3") (pin "TP1") (pinfunction "TP1_GND_TP1") (pintype "power_in+no_connect"))
    )
    (net (code "58") (name "unconnected-(U3-TP2_USB_DM-PadTP2)") (class "Default")
      (node (ref "U3") (pin "TP2") (pinfunction "TP2_USB_DM_TP2") (pintype "bidirectional+no_connect"))
    )
    (net (code "59") (name "unconnected-(U3-TP3_USB_DP-PadTP3)") (class "Default")
      (node (ref "U3") (pin "TP3") (pinfunction "TP3_USB_DP_TP3") (pintype "bidirectional+no_connect"))
    )
    (net (code "60") (name "unconnected-(U3-TP4_GPIO23{slash}SMPS_PS-PadTP4)") (class "Default")
      (node (ref "U3") (pin "TP4") (pinfunction "TP4_GPIO23/SMPS_PS_TP4") (pintype "passive+no_connect"))
    )
    (net (code "61") (name "unconnected-(U3-TP5_GPIO25{slash}LED-PadTP5)") (class "Default")
      (node (ref "U3") (pin "TP5") (pinfunction "TP5_GPIO25/LED_TP5") (pintype "output+no_connect"))
    )
    (net (code "62") (name "unconnected-(U3-TP6_BOOTSEL-PadTP6)") (class "Default")
      (node (ref "U3") (pin "TP6") (pinfunction "TP6_BOOTSEL_TP6") (pintype "input+no_connect"))
    )
    (net (code "63") (name "unconnected-(U3-USB_SHIELD-PadA)") (class "Default")
      (node (ref "U3") (pin "A") (pinfunction "USB_SHIELD_A") (pintype "power_in+no_connect"))
    )
    (net (code "64") (name "unconnected-(U3-USB_SHIELD-PadB)") (class "Default")
      (node (ref "U3") (pin "B") (pinfunction "USB_SHIELD_B") (pintype "power_in+no_connect"))
    )
    (net (code "65") (name "unconnected-(U3-USB_SHIELD-PadC)") (class "Default")
      (node (ref "U3") (pin "C") (pinfunction "USB_SHIELD_C") (pintype "power_in+no_connect"))
    )
    (net (code "66") (name "unconnected-(U3-USB_SHIELD-PadD)") (class "Default")
      (node (ref "U3") (pin "D") (pinfunction "USB_SHIELD_D") (pintype "power_in+no_connect"))
    )
    (net (code "67") (name "unconnected-(U3-VBUS-Pad40)") (class "Default")
      (node (ref "U3") (pin "40") (pinfunction "VBUS_40") (pintype "power_in+no_connect"))
    )
    (net (code "68") (name "unconnected-(U5-NC-Pad4)") (class "Default")
      (node (ref "U5") (pin "4") (pinfunction "NC_4") (pintype "passive+no_connect"))
    )
    (net (code "69") (name "unconnected-(U6-LNA_EN-Pad4)") (class "Default")
      (node (ref "U6") (pin "4") (pinfunction "LNA_EN_4") (pintype "input+no_connect"))
    )
    (net (code "70") (name "unconnected-(U6-SAFEBOOT-Pad3)") (class "Default")
      (node (ref "U6") (pin "3") (pinfunction "SAFEBOOT_3") (pintype "input+no_connect"))
    )
    (net (code "71") (name "unconnected-(U6-TIMEPULS-Pad6)") (class "Default")
      (node (ref "U6") (pin "6") (pinfunction "TIMEPULS_6") (pintype "input+no_connect"))
    )
  )
)
